# 06_ZYNQ_CAMERALINK.net
KiCad netlist of a schematic drawn in Altium Designer
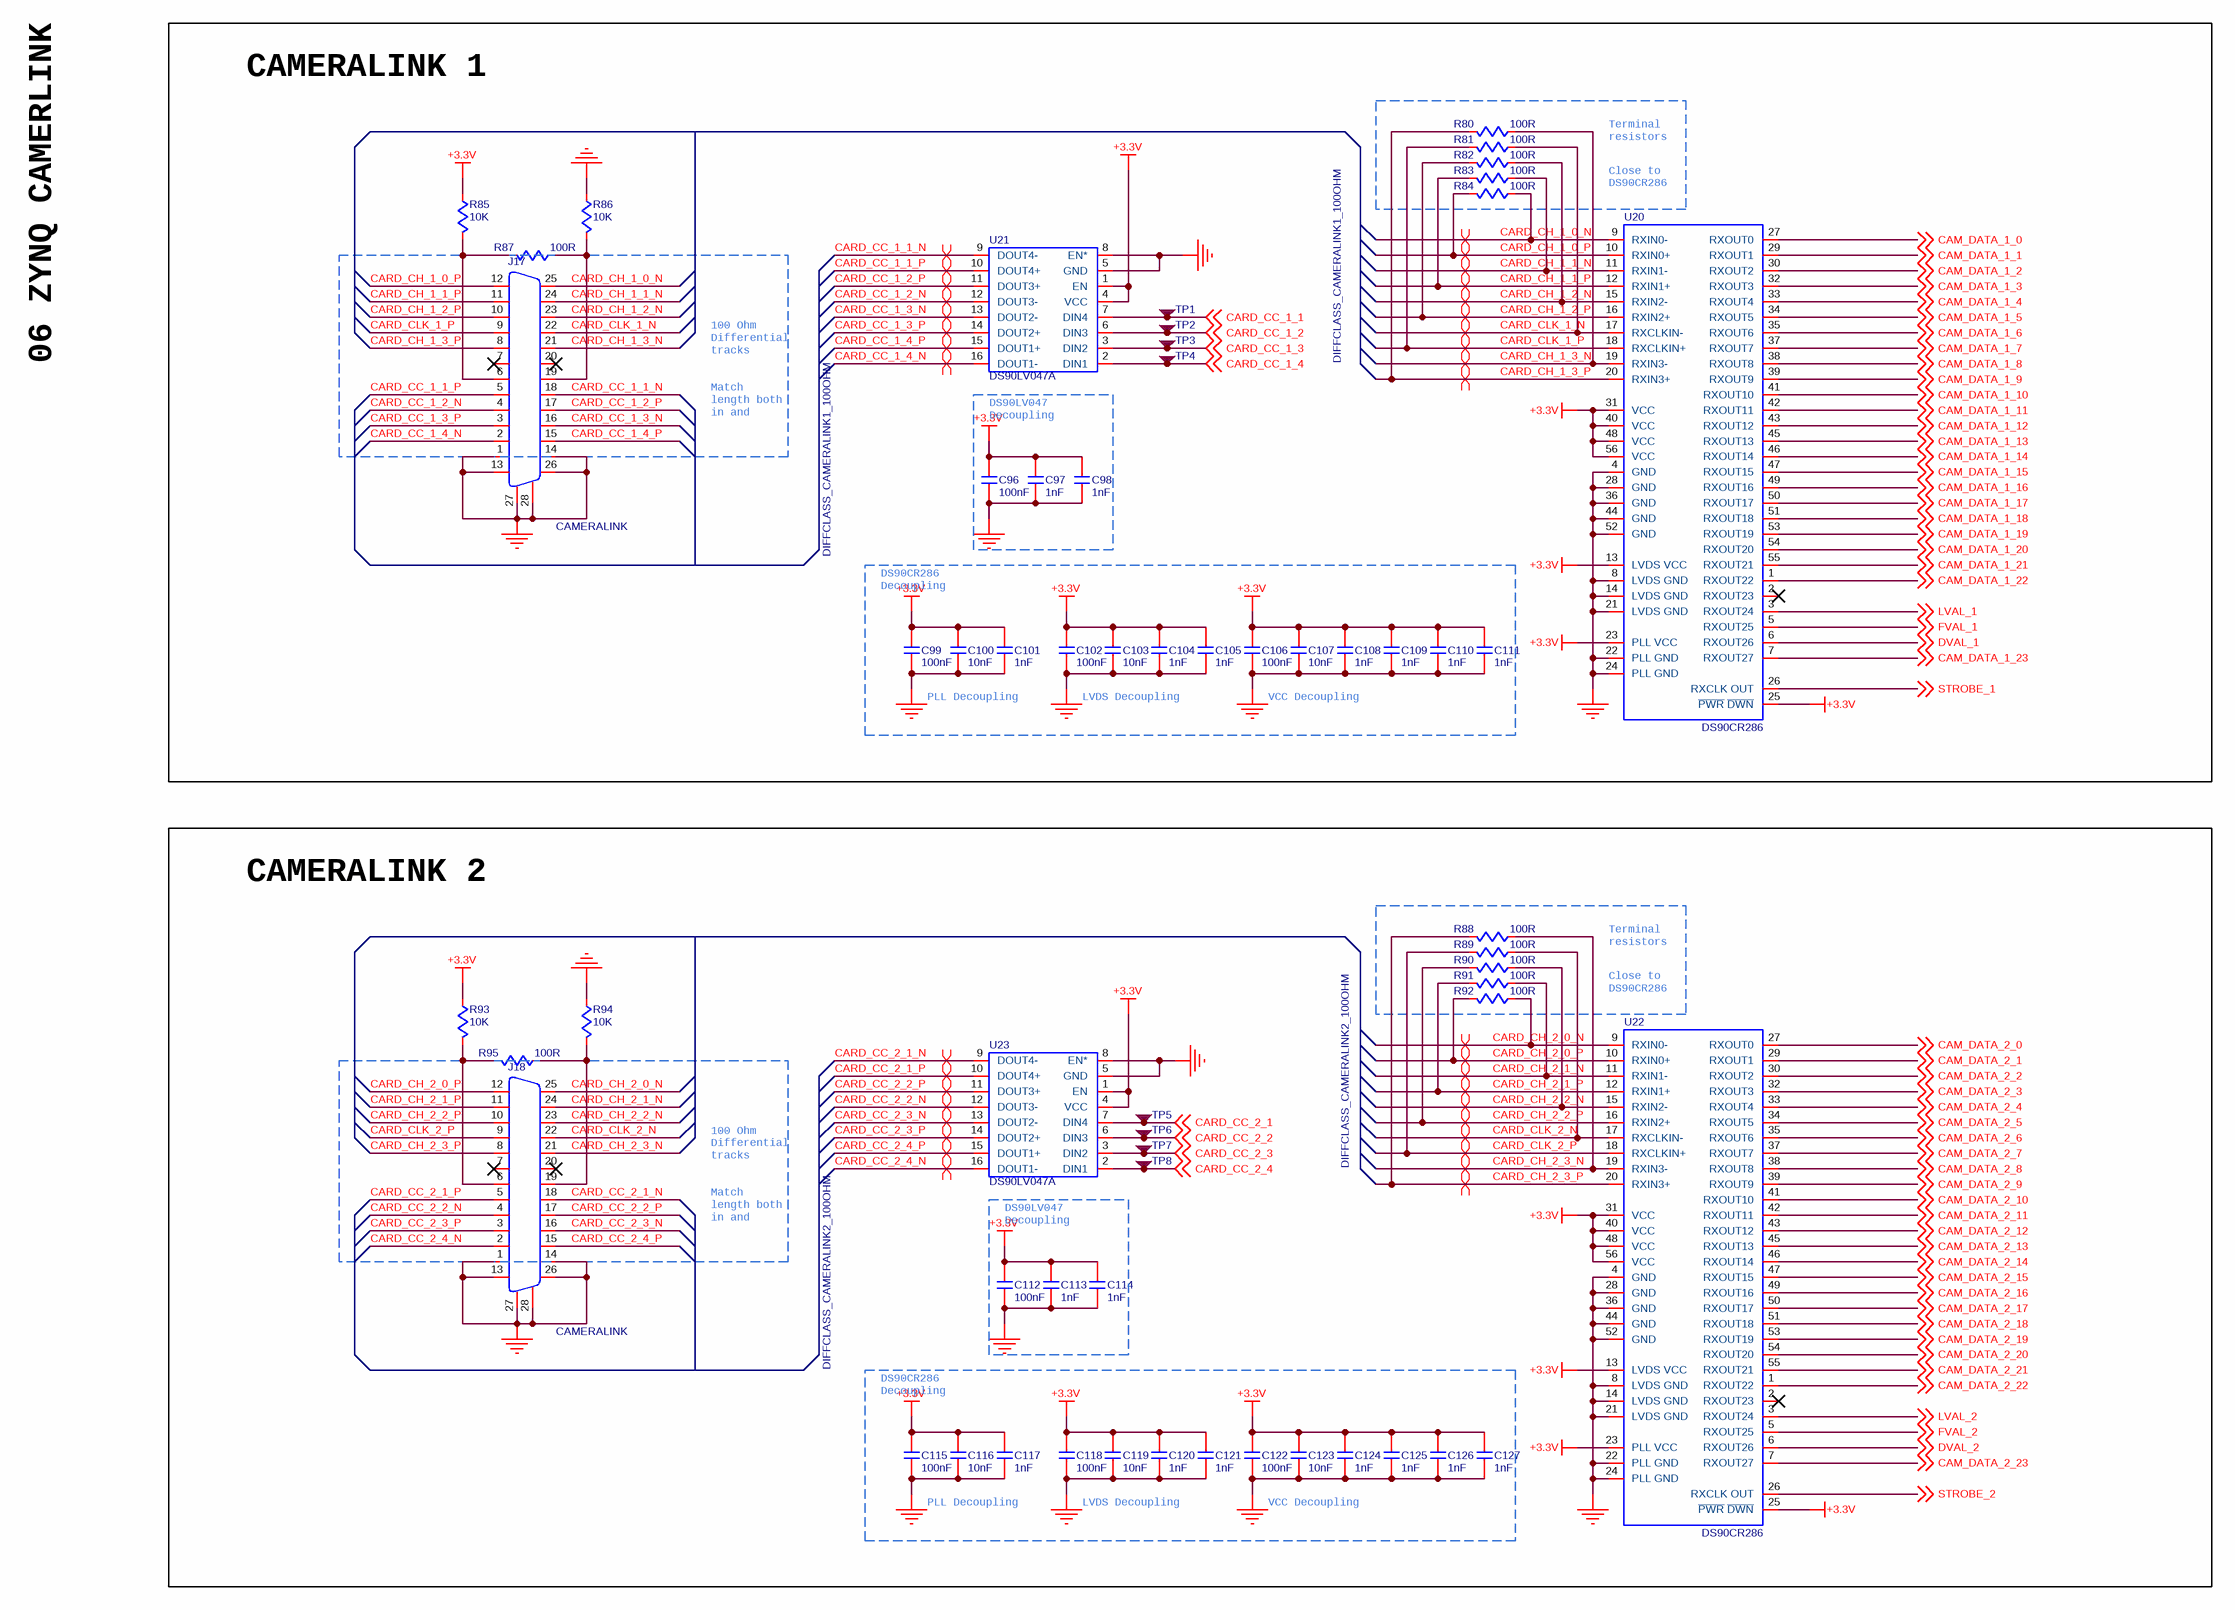
[diagram p0: 06_ZYNQ_CAMERALINK.SchDoc]

(export (version "E")
  (design (tool "Eeschema 10.0.6"))
  (components
    (comp (ref "C96")
      (value "100nF")
      (footprint "zynq:C0402")
      (fields (field (name "VOLTAGE") "25V") (field (name "Comment") "C-NOMO"))
      (libsource (lib "zynq") (part "C-NOMO"))
    )
    (comp (ref "C97")
      (value "1nF")
      (footprint "zynq:C0402")
      (fields (field (name "VOLTAGE") "25V") (field (name "Comment") "C-NOMO"))
      (libsource (lib "zynq") (part "C-NOMO"))
    )
    (comp (ref "C98")
      (value "1nF")
      (footprint "zynq:C0402")
      (fields (field (name "VOLTAGE") "25V") (field (name "Comment") "C-NOMO"))
      (libsource (lib "zynq") (part "C-NOMO"))
    )
    (comp (ref "C99")
      (value "100nF")
      (footprint "zynq:C0402")
      (fields (field (name "VOLTAGE") "25V") (field (name "Comment") "C-NOMO"))
      (libsource (lib "zynq") (part "C-NOMO"))
    )
    (comp (ref "C100")
      (value "10nF")
      (footprint "zynq:C0402")
      (fields (field (name "VOLTAGE") "25V") (field (name "Comment") "C-NOMO"))
      (libsource (lib "zynq") (part "C-NOMO"))
    )
    (comp (ref "C101")
      (value "1nF")
      (footprint "zynq:C0402")
      (fields (field (name "VOLTAGE") "25V") (field (name "Comment") "C-NOMO"))
      (libsource (lib "zynq") (part "C-NOMO"))
    )
    (comp (ref "C102")
      (value "100nF")
      (footprint "zynq:C0402")
      (fields (field (name "VOLTAGE") "25V") (field (name "Comment") "C-NOMO"))
      (libsource (lib "zynq") (part "C-NOMO"))
    )
    (comp (ref "C103")
      (value "10nF")
      (footprint "zynq:C0402")
      (fields (field (name "VOLTAGE") "25V") (field (name "Comment") "C-NOMO"))
      (libsource (lib "zynq") (part "C-NOMO"))
    )
    (comp (ref "C104")
      (value "1nF")
      (footprint "zynq:C0402")
      (fields (field (name "VOLTAGE") "25V") (field (name "Comment") "C-NOMO"))
      (libsource (lib "zynq") (part "C-NOMO"))
    )
    (comp (ref "C105")
      (value "1nF")
      (footprint "zynq:C0402")
      (fields (field (name "VOLTAGE") "25V") (field (name "Comment") "C-NOMO"))
      (libsource (lib "zynq") (part "C-NOMO"))
    )
    (comp (ref "C106")
      (value "100nF")
      (footprint "zynq:C0402")
      (fields (field (name "VOLTAGE") "25V") (field (name "Comment") "C-NOMO"))
      (libsource (lib "zynq") (part "C-NOMO"))
    )
    (comp (ref "C107")
      (value "10nF")
      (footprint "zynq:C0402")
      (fields (field (name "VOLTAGE") "25V") (field (name "Comment") "C-NOMO"))
      (libsource (lib "zynq") (part "C-NOMO"))
    )
    (comp (ref "C108")
      (value "1nF")
      (footprint "zynq:C0402")
      (fields (field (name "VOLTAGE") "25V") (field (name "Comment") "C-NOMO"))
      (libsource (lib "zynq") (part "C-NOMO"))
    )
    (comp (ref "C109")
      (value "1nF")
      (footprint "zynq:C0402")
      (fields (field (name "VOLTAGE") "25V") (field (name "Comment") "C-NOMO"))
      (libsource (lib "zynq") (part "C-NOMO"))
    )
    (comp (ref "C110")
      (value "1nF")
      (footprint "zynq:C0402")
      (fields (field (name "VOLTAGE") "25V") (field (name "Comment") "C-NOMO"))
      (libsource (lib "zynq") (part "C-NOMO"))
    )
    (comp (ref "C111")
      (value "1nF")
      (footprint "zynq:C0402")
      (fields (field (name "VOLTAGE") "25V") (field (name "Comment") "C-NOMO"))
      (libsource (lib "zynq") (part "C-NOMO"))
    )
    (comp (ref "C112")
      (value "100nF")
      (footprint "zynq:C0402")
      (fields (field (name "VOLTAGE") "25V") (field (name "Comment") "C-NOMO"))
      (libsource (lib "zynq") (part "C-NOMO"))
    )
    (comp (ref "C113")
      (value "1nF")
      (footprint "zynq:C0402")
      (fields (field (name "VOLTAGE") "25V") (field (name "Comment") "C-NOMO"))
      (libsource (lib "zynq") (part "C-NOMO"))
    )
    (comp (ref "C114")
      (value "1nF")
      (footprint "zynq:C0402")
      (fields (field (name "VOLTAGE") "25V") (field (name "Comment") "C-NOMO"))
      (libsource (lib "zynq") (part "C-NOMO"))
    )
    (comp (ref "C115")
      (value "100nF")
      (footprint "zynq:C0402")
      (fields (field (name "VOLTAGE") "25V") (field (name "Comment") "C-NOMO"))
      (libsource (lib "zynq") (part "C-NOMO"))
    )
    (comp (ref "C116")
      (value "10nF")
      (footprint "zynq:C0402")
      (fields (field (name "VOLTAGE") "25V") (field (name "Comment") "C-NOMO"))
      (libsource (lib "zynq") (part "C-NOMO"))
    )
    (comp (ref "C117")
      (value "1nF")
      (footprint "zynq:C0402")
      (fields (field (name "VOLTAGE") "25V") (field (name "Comment") "C-NOMO"))
      (libsource (lib "zynq") (part "C-NOMO"))
    )
    (comp (ref "C118")
      (value "100nF")
      (footprint "zynq:C0402")
      (fields (field (name "VOLTAGE") "25V") (field (name "Comment") "C-NOMO"))
      (libsource (lib "zynq") (part "C-NOMO"))
    )
    (comp (ref "C119")
      (value "10nF")
      (footprint "zynq:C0402")
      (fields (field (name "VOLTAGE") "25V") (field (name "Comment") "C-NOMO"))
      (libsource (lib "zynq") (part "C-NOMO"))
    )
    (comp (ref "C120")
      (value "1nF")
      (footprint "zynq:C0402")
      (fields (field (name "VOLTAGE") "25V") (field (name "Comment") "C-NOMO"))
      (libsource (lib "zynq") (part "C-NOMO"))
    )
    (comp (ref "C121")
      (value "1nF")
      (footprint "zynq:C0402")
      (fields (field (name "VOLTAGE") "25V") (field (name "Comment") "C-NOMO"))
      (libsource (lib "zynq") (part "C-NOMO"))
    )
    (comp (ref "C122")
      (value "100nF")
      (footprint "zynq:C0402")
      (fields (field (name "VOLTAGE") "25V") (field (name "Comment") "C-NOMO"))
      (libsource (lib "zynq") (part "C-NOMO"))
    )
    (comp (ref "C123")
      (value "10nF")
      (footprint "zynq:C0402")
      (fields (field (name "VOLTAGE") "25V") (field (name "Comment") "C-NOMO"))
      (libsource (lib "zynq") (part "C-NOMO"))
    )
    (comp (ref "C124")
      (value "1nF")
      (footprint "zynq:C0402")
      (fields (field (name "VOLTAGE") "25V") (field (name "Comment") "C-NOMO"))
      (libsource (lib "zynq") (part "C-NOMO"))
    )
    (comp (ref "C125")
      (value "1nF")
      (footprint "zynq:C0402")
      (fields (field (name "VOLTAGE") "25V") (field (name "Comment") "C-NOMO"))
      (libsource (lib "zynq") (part "C-NOMO"))
    )
    (comp (ref "C126")
      (value "1nF")
      (footprint "zynq:C0402")
      (fields (field (name "VOLTAGE") "25V") (field (name "Comment") "C-NOMO"))
      (libsource (lib "zynq") (part "C-NOMO"))
    )
    (comp (ref "C127")
      (value "1nF")
      (footprint "zynq:C0402")
      (fields (field (name "VOLTAGE") "25V") (field (name "Comment") "C-NOMO"))
      (libsource (lib "zynq") (part "C-NOMO"))
    )
    (comp (ref "J17")
      (value "CAMERALINK")
      (footprint "zynq:CAMERALINK")
      (libsource (lib "zynq") (part "CAMERALINK"))
    )
    (comp (ref "J18")
      (value "CAMERALINK")
      (footprint "zynq:CAMERALINK")
      (libsource (lib "zynq") (part "CAMERALINK"))
    )
    (comp (ref "R80")
      (value "100R")
      (footprint "zynq:R0402")
      (fields (field (name "Comment") "R"))
      (libsource (lib "zynq") (part "R"))
    )
    (comp (ref "R81")
      (value "100R")
      (footprint "zynq:R0402")
      (fields (field (name "Comment") "R"))
      (libsource (lib "zynq") (part "R"))
    )
    (comp (ref "R82")
      (value "100R")
      (footprint "zynq:R0402")
      (fields (field (name "Comment") "R"))
      (libsource (lib "zynq") (part "R"))
    )
    (comp (ref "R83")
      (value "100R")
      (footprint "zynq:R0402")
      (fields (field (name "Comment") "R"))
      (libsource (lib "zynq") (part "R"))
    )
    (comp (ref "R84")
      (value "100R")
      (footprint "zynq:R0402")
      (fields (field (name "Comment") "R"))
      (libsource (lib "zynq") (part "R"))
    )
    (comp (ref "R85")
      (value "10K")
      (footprint "zynq:R0402")
      (fields (field (name "Comment") "R"))
      (libsource (lib "zynq") (part "R"))
    )
    (comp (ref "R86")
      (value "10K")
      (footprint "zynq:R0402")
      (fields (field (name "Comment") "R"))
      (libsource (lib "zynq") (part "R"))
    )
    (comp (ref "R87")
      (value "100R")
      (footprint "zynq:R0402")
      (fields (field (name "Comment") "R"))
      (libsource (lib "zynq") (part "R"))
    )
    (comp (ref "R88")
      (value "100R")
      (footprint "zynq:R0402")
      (fields (field (name "Comment") "R"))
      (libsource (lib "zynq") (part "R"))
    )
    (comp (ref "R89")
      (value "100R")
      (footprint "zynq:R0402")
      (fields (field (name "Comment") "R"))
      (libsource (lib "zynq") (part "R"))
    )
    (comp (ref "R90")
      (value "100R")
      (footprint "zynq:R0402")
      (fields (field (name "Comment") "R"))
      (libsource (lib "zynq") (part "R"))
    )
    (comp (ref "R91")
      (value "100R")
      (footprint "zynq:R0402")
      (fields (field (name "Comment") "R"))
      (libsource (lib "zynq") (part "R"))
    )
    (comp (ref "R92")
      (value "100R")
      (footprint "zynq:R0402")
      (fields (field (name "Comment") "R"))
      (libsource (lib "zynq") (part "R"))
    )
    (comp (ref "R93")
      (value "10K")
      (footprint "zynq:R0402")
      (fields (field (name "Comment") "R"))
      (libsource (lib "zynq") (part "R"))
    )
    (comp (ref "R94")
      (value "10K")
      (footprint "zynq:R0402")
      (fields (field (name "Comment") "R"))
      (libsource (lib "zynq") (part "R"))
    )
    (comp (ref "R95")
      (value "100R")
      (footprint "zynq:R0402")
      (fields (field (name "Comment") "R"))
      (libsource (lib "zynq") (part "R"))
    )
    (comp (ref "TP1") (value "TP") (footprint "zynq:TP") (libsource (lib "zynq") (part "TP")))
    (comp (ref "TP2") (value "TP") (footprint "zynq:TP") (libsource (lib "zynq") (part "TP")))
    (comp (ref "TP3") (value "TP") (footprint "zynq:TP") (libsource (lib "zynq") (part "TP")))
    (comp (ref "TP4") (value "TP") (footprint "zynq:TP") (libsource (lib "zynq") (part "TP")))
    (comp (ref "TP5") (value "TP") (footprint "zynq:TP") (libsource (lib "zynq") (part "TP")))
    (comp (ref "TP6") (value "TP") (footprint "zynq:TP") (libsource (lib "zynq") (part "TP")))
    (comp (ref "TP7") (value "TP") (footprint "zynq:TP") (libsource (lib "zynq") (part "TP")))
    (comp (ref "TP8") (value "TP") (footprint "zynq:TP") (libsource (lib "zynq") (part "TP")))
    (comp (ref "U20")
      (value "DS90CR286")
      (footprint "zynq:DS90CR286")
      (libsource (lib "zynq") (part "DS90CR286"))
    )
    (comp (ref "U21")
      (value "DS90LV047A")
      (footprint "zynq:DS90LV047")
      (libsource (lib "zynq") (part "DS90LV047A"))
    )
    (comp (ref "U22")
      (value "DS90CR286")
      (footprint "zynq:DS90CR286")
      (libsource (lib "zynq") (part "DS90CR286"))
    )
    (comp (ref "U23")
      (value "DS90LV047A")
      (footprint "zynq:DS90LV047")
      (libsource (lib "zynq") (part "DS90LV047A"))
    )
  )
  (nets
    (net (code "1") (name "+3.3V") (class "Default")
      (node (ref "C100") (pin "2") (pinfunction "2_2") (pintype "passive"))
      (node (ref "C101") (pin "2") (pinfunction "2_2") (pintype "passive"))
      (node (ref "C102") (pin "2") (pinfunction "2_2") (pintype "passive"))
      (node (ref "C103") (pin "2") (pinfunction "2_2") (pintype "passive"))
      (node (ref "C104") (pin "2") (pinfunction "2_2") (pintype "passive"))
      (node (ref "C105") (pin "2") (pinfunction "2_2") (pintype "passive"))
      (node (ref "C106") (pin "2") (pinfunction "2_2") (pintype "passive"))
      (node (ref "C107") (pin "2") (pinfunction "2_2") (pintype "passive"))
      (node (ref "C108") (pin "2") (pinfunction "2_2") (pintype "passive"))
      (node (ref "C109") (pin "2") (pinfunction "2_2") (pintype "passive"))
      (node (ref "C110") (pin "2") (pinfunction "2_2") (pintype "passive"))
      (node (ref "C111") (pin "2") (pinfunction "2_2") (pintype "passive"))
      (node (ref "C112") (pin "2") (pinfunction "2_2") (pintype "passive"))
      (node (ref "C113") (pin "2") (pinfunction "2_2") (pintype "passive"))
      (node (ref "C114") (pin "2") (pinfunction "2_2") (pintype "passive"))
      (node (ref "C115") (pin "2") (pinfunction "2_2") (pintype "passive"))
      (node (ref "C116") (pin "2") (pinfunction "2_2") (pintype "passive"))
      (node (ref "C117") (pin "2") (pinfunction "2_2") (pintype "passive"))
      (node (ref "C118") (pin "2") (pinfunction "2_2") (pintype "passive"))
      (node (ref "C119") (pin "2") (pinfunction "2_2") (pintype "passive"))
      (node (ref "C120") (pin "2") (pinfunction "2_2") (pintype "passive"))
      (node (ref "C121") (pin "2") (pinfunction "2_2") (pintype "passive"))
      (node (ref "C122") (pin "2") (pinfunction "2_2") (pintype "passive"))
      (node (ref "C123") (pin "2") (pinfunction "2_2") (pintype "passive"))
      (node (ref "C124") (pin "2") (pinfunction "2_2") (pintype "passive"))
      (node (ref "C125") (pin "2") (pinfunction "2_2") (pintype "passive"))
      (node (ref "C126") (pin "2") (pinfunction "2_2") (pintype "passive"))
      (node (ref "C127") (pin "2") (pinfunction "2_2") (pintype "passive"))
      (node (ref "C96") (pin "2") (pinfunction "2_2") (pintype "passive"))
      (node (ref "C97") (pin "2") (pinfunction "2_2") (pintype "passive"))
      (node (ref "C98") (pin "2") (pinfunction "2_2") (pintype "passive"))
      (node (ref "C99") (pin "2") (pinfunction "2_2") (pintype "passive"))
      (node (ref "R85") (pin "2") (pinfunction "2_2") (pintype "passive"))
      (node (ref "R93") (pin "2") (pinfunction "2_2") (pintype "passive"))
      (node (ref "U20") (pin "13") (pinfunction "LVDS_VCC_13") (pintype "passive"))
      (node (ref "U20") (pin "23") (pinfunction "PLL_VCC_23") (pintype "passive"))
      (node (ref "U20") (pin "25") (pinfunction "~{PWR}_~{DWN}_25") (pintype "passive"))
      (node (ref "U20") (pin "31") (pinfunction "VCC_31") (pintype "passive"))
      (node (ref "U20") (pin "40") (pinfunction "VCC_40") (pintype "passive"))
      (node (ref "U20") (pin "48") (pinfunction "VCC_48") (pintype "passive"))
      (node (ref "U20") (pin "56") (pinfunction "VCC_56") (pintype "passive"))
      (node (ref "U21") (pin "1") (pinfunction "EN_1") (pintype "passive"))
      (node (ref "U21") (pin "4") (pinfunction "VCC_4") (pintype "passive"))
      (node (ref "U22") (pin "13") (pinfunction "LVDS_VCC_13") (pintype "passive"))
      (node (ref "U22") (pin "23") (pinfunction "PLL_VCC_23") (pintype "passive"))
      (node (ref "U22") (pin "25") (pinfunction "~{PWR}_~{DWN}_25") (pintype "passive"))
      (node (ref "U22") (pin "31") (pinfunction "VCC_31") (pintype "passive"))
      (node (ref "U22") (pin "40") (pinfunction "VCC_40") (pintype "passive"))
      (node (ref "U22") (pin "48") (pinfunction "VCC_48") (pintype "passive"))
      (node (ref "U22") (pin "56") (pinfunction "VCC_56") (pintype "passive"))
      (node (ref "U23") (pin "1") (pinfunction "EN_1") (pintype "passive"))
      (node (ref "U23") (pin "4") (pinfunction "VCC_4") (pintype "passive"))
    )
    (net (code "2") (name "/CARD_CC_1_1_N") (class "Default")
      (node (ref "J17") (pin "18") (pintype "passive"))
      (node (ref "U21") (pin "9") (pinfunction "DOUT4-_9") (pintype "passive"))
    )
    (net (code "3") (name "/CARD_CC_1_1_P") (class "Default")
      (node (ref "J17") (pin "5") (pintype "passive"))
      (node (ref "U21") (pin "10") (pinfunction "DOUT4+_10") (pintype "passive"))
    )
    (net (code "4") (name "/CARD_CC_1_2_N") (class "Default")
      (node (ref "J17") (pin "4") (pintype "passive"))
      (node (ref "U21") (pin "12") (pinfunction "DOUT3-_12") (pintype "passive"))
    )
    (net (code "5") (name "/CARD_CC_1_2_P") (class "Default")
      (node (ref "J17") (pin "17") (pintype "passive"))
      (node (ref "U21") (pin "11") (pinfunction "DOUT3+_11") (pintype "passive"))
    )
    (net (code "6") (name "/CARD_CC_1_3_N") (class "Default")
      (node (ref "J17") (pin "16") (pintype "passive"))
      (node (ref "U21") (pin "13") (pinfunction "DOUT2-_13") (pintype "passive"))
    )
    (net (code "7") (name "/CARD_CC_1_3_P") (class "Default")
      (node (ref "J17") (pin "3") (pintype "passive"))
      (node (ref "U21") (pin "14") (pinfunction "DOUT2+_14") (pintype "passive"))
    )
    (net (code "8") (name "/CARD_CC_1_4_N") (class "Default")
      (node (ref "J17") (pin "2") (pintype "passive"))
      (node (ref "U21") (pin "16") (pinfunction "DOUT1-_16") (pintype "passive"))
    )
    (net (code "9") (name "/CARD_CC_1_4_P") (class "Default")
      (node (ref "J17") (pin "15") (pintype "passive"))
      (node (ref "U21") (pin "15") (pinfunction "DOUT1+_15") (pintype "passive"))
    )
    (net (code "10") (name "/CARD_CC_2_1_N") (class "Default")
      (node (ref "J18") (pin "18") (pintype "passive"))
      (node (ref "U23") (pin "9") (pinfunction "DOUT4-_9") (pintype "passive"))
    )
    (net (code "11") (name "/CARD_CC_2_1_P") (class "Default")
      (node (ref "J18") (pin "5") (pintype "passive"))
      (node (ref "U23") (pin "10") (pinfunction "DOUT4+_10") (pintype "passive"))
    )
    (net (code "12") (name "/CARD_CC_2_2_N") (class "Default")
      (node (ref "J18") (pin "4") (pintype "passive"))
      (node (ref "U23") (pin "12") (pinfunction "DOUT3-_12") (pintype "passive"))
    )
    (net (code "13") (name "/CARD_CC_2_2_P") (class "Default")
      (node (ref "J18") (pin "17") (pintype "passive"))
      (node (ref "U23") (pin "11") (pinfunction "DOUT3+_11") (pintype "passive"))
    )
    (net (code "14") (name "/CARD_CC_2_3_N") (class "Default")
      (node (ref "J18") (pin "16") (pintype "passive"))
      (node (ref "U23") (pin "13") (pinfunction "DOUT2-_13") (pintype "passive"))
    )
    (net (code "15") (name "/CARD_CC_2_3_P") (class "Default")
      (node (ref "J18") (pin "3") (pintype "passive"))
      (node (ref "U23") (pin "14") (pinfunction "DOUT2+_14") (pintype "passive"))
    )
    (net (code "16") (name "/CARD_CC_2_4_N") (class "Default")
      (node (ref "J18") (pin "2") (pintype "passive"))
      (node (ref "U23") (pin "16") (pinfunction "DOUT1-_16") (pintype "passive"))
    )
    (net (code "17") (name "/CARD_CC_2_4_P") (class "Default")
      (node (ref "J18") (pin "15") (pintype "passive"))
      (node (ref "U23") (pin "15") (pinfunction "DOUT1+_15") (pintype "passive"))
    )
    (net (code "18") (name "/CARD_CH_1_0_N") (class "Default")
      (node (ref "J17") (pin "25") (pintype "passive"))
      (node (ref "R84") (pin "2") (pinfunction "2_2") (pintype "passive"))
      (node (ref "U20") (pin "9") (pinfunction "RXIN0-_9") (pintype "passive"))
    )
    (net (code "19") (name "/CARD_CH_1_0_P") (class "Default")
      (node (ref "J17") (pin "12") (pintype "passive"))
      (node (ref "R84") (pin "1") (pinfunction "1_1") (pintype "passive"))
      (node (ref "U20") (pin "10") (pinfunction "RXIN0+_10") (pintype "passive"))
    )
    (net (code "20") (name "/CARD_CH_1_1_N") (class "Default")
      (node (ref "J17") (pin "24") (pintype "passive"))
      (node (ref "R83") (pin "2") (pinfunction "2_2") (pintype "passive"))
      (node (ref "U20") (pin "11") (pinfunction "RXIN1-_11") (pintype "passive"))
    )
    (net (code "21") (name "/CARD_CH_1_1_P") (class "Default")
      (node (ref "J17") (pin "11") (pintype "passive"))
      (node (ref "R83") (pin "1") (pinfunction "1_1") (pintype "passive"))
      (node (ref "U20") (pin "12") (pinfunction "RXIN1+_12") (pintype "passive"))
    )
    (net (code "22") (name "/CARD_CH_1_2_N") (class "Default")
      (node (ref "J17") (pin "23") (pintype "passive"))
      (node (ref "R82") (pin "2") (pinfunction "2_2") (pintype "passive"))
      (node (ref "U20") (pin "15") (pinfunction "RXIN2-_15") (pintype "passive"))
    )
    (net (code "23") (name "/CARD_CH_1_2_P") (class "Default")
      (node (ref "J17") (pin "10") (pintype "passive"))
      (node (ref "R82") (pin "1") (pinfunction "1_1") (pintype "passive"))
      (node (ref "U20") (pin "16") (pinfunction "RXIN2+_16") (pintype "passive"))
    )
    (net (code "24") (name "/CARD_CH_1_3_N") (class "Default")
      (node (ref "J17") (pin "21") (pintype "passive"))
      (node (ref "R80") (pin "2") (pinfunction "2_2") (pintype "passive"))
      (node (ref "U20") (pin "19") (pinfunction "RXIN3-_19") (pintype "passive"))
    )
    (net (code "25") (name "/CARD_CH_1_3_P") (class "Default")
      (node (ref "J17") (pin "8") (pintype "passive"))
      (node (ref "R80") (pin "1") (pinfunction "1_1") (pintype "passive"))
      (node (ref "U20") (pin "20") (pinfunction "RXIN3+_20") (pintype "passive"))
    )
    (net (code "26") (name "/CARD_CH_2_0_N") (class "Default")
      (node (ref "J18") (pin "25") (pintype "passive"))
      (node (ref "R92") (pin "2") (pinfunction "2_2") (pintype "passive"))
      (node (ref "U22") (pin "9") (pinfunction "RXIN0-_9") (pintype "passive"))
    )
    (net (code "27") (name "/CARD_CH_2_0_P") (class "Default")
      (node (ref "J18") (pin "12") (pintype "passive"))
      (node (ref "R92") (pin "1") (pinfunction "1_1") (pintype "passive"))
      (node (ref "U22") (pin "10") (pinfunction "RXIN0+_10") (pintype "passive"))
    )
    (net (code "28") (name "/CARD_CH_2_1_N") (class "Default")
      (node (ref "J18") (pin "24") (pintype "passive"))
      (node (ref "R91") (pin "2") (pinfunction "2_2") (pintype "passive"))
      (node (ref "U22") (pin "11") (pinfunction "RXIN1-_11") (pintype "passive"))
    )
    (net (code "29") (name "/CARD_CH_2_1_P") (class "Default")
      (node (ref "J18") (pin "11") (pintype "passive"))
      (node (ref "R91") (pin "1") (pinfunction "1_1") (pintype "passive"))
      (node (ref "U22") (pin "12") (pinfunction "RXIN1+_12") (pintype "passive"))
    )
    (net (code "30") (name "/CARD_CH_2_2_N") (class "Default")
      (node (ref "J18") (pin "23") (pintype "passive"))
      (node (ref "R90") (pin "2") (pinfunction "2_2") (pintype "passive"))
      (node (ref "U22") (pin "15") (pinfunction "RXIN2-_15") (pintype "passive"))
    )
    (net (code "31") (name "/CARD_CH_2_2_P") (class "Default")
      (node (ref "J18") (pin "10") (pintype "passive"))
      (node (ref "R90") (pin "1") (pinfunction "1_1") (pintype "passive"))
      (node (ref "U22") (pin "16") (pinfunction "RXIN2+_16") (pintype "passive"))
    )
    (net (code "32") (name "/CARD_CH_2_3_N") (class "Default")
      (node (ref "J18") (pin "21") (pintype "passive"))
      (node (ref "R88") (pin "2") (pinfunction "2_2") (pintype "passive"))
      (node (ref "U22") (pin "19") (pinfunction "RXIN3-_19") (pintype "passive"))
    )
    (net (code "33") (name "/CARD_CH_2_3_P") (class "Default")
      (node (ref "J18") (pin "8") (pintype "passive"))
      (node (ref "R88") (pin "1") (pinfunction "1_1") (pintype "passive"))
      (node (ref "U22") (pin "20") (pinfunction "RXIN3+_20") (pintype "passive"))
    )
    (net (code "34") (name "/CARD_CLK_1_N") (class "Default")
      (node (ref "J17") (pin "22") (pintype "passive"))
      (node (ref "R81") (pin "2") (pinfunction "2_2") (pintype "passive"))
      (node (ref "U20") (pin "17") (pinfunction "RXCLKIN-_17") (pintype "passive"))
    )
    (net (code "35") (name "/CARD_CLK_1_P") (class "Default")
      (node (ref "J17") (pin "9") (pintype "passive"))
      (node (ref "R81") (pin "1") (pinfunction "1_1") (pintype "passive"))
      (node (ref "U20") (pin "18") (pinfunction "RXCLKIN+_18") (pintype "passive"))
    )
    (net (code "36") (name "/CARD_CLK_2_N") (class "Default")
      (node (ref "J18") (pin "22") (pintype "passive"))
      (node (ref "R89") (pin "2") (pinfunction "2_2") (pintype "passive"))
      (node (ref "U22") (pin "17") (pinfunction "RXCLKIN-_17") (pintype "passive"))
    )
    (net (code "37") (name "/CARD_CLK_2_P") (class "Default")
      (node (ref "J18") (pin "9") (pintype "passive"))
      (node (ref "R89") (pin "1") (pinfunction "1_1") (pintype "passive"))
      (node (ref "U22") (pin "18") (pinfunction "RXCLKIN+_18") (pintype "passive"))
    )
    (net (code "38") (name "CAM_DATA_1_0") (class "Default")
      (node (ref "U20") (pin "27") (pinfunction "RXOUT0_27") (pintype "passive"))
    )
    (net (code "39") (name "CAM_DATA_1_1") (class "Default")
      (node (ref "U20") (pin "29") (pinfunction "RXOUT1_29") (pintype "passive"))
    )
    (net (code "40") (name "CAM_DATA_1_2") (class "Default")
      (node (ref "U20") (pin "30") (pinfunction "RXOUT2_30") (pintype "passive"))
    )
    (net (code "41") (name "CAM_DATA_1_3") (class "Default")
      (node (ref "U20") (pin "32") (pinfunction "RXOUT3_32") (pintype "passive"))
    )
    (net (code "42") (name "CAM_DATA_1_4") (class "Default")
      (node (ref "U20") (pin "33") (pinfunction "RXOUT4_33") (pintype "passive"))
    )
    (net (code "43") (name "CAM_DATA_1_5") (class "Default")
      (node (ref "U20") (pin "34") (pinfunction "RXOUT5_34") (pintype "passive"))
    )
    (net (code "44") (name "CAM_DATA_1_6") (class "Default")
      (node (ref "U20") (pin "35") (pinfunction "RXOUT6_35") (pintype "passive"))
    )
    (net (code "45") (name "CAM_DATA_1_7") (class "Default")
      (node (ref "U20") (pin "37") (pinfunction "RXOUT7_37") (pintype "passive"))
    )
    (net (code "46") (name "CAM_DATA_1_8") (class "Default")
      (node (ref "U20") (pin "38") (pinfunction "RXOUT8_38") (pintype "passive"))
    )
    (net (code "47") (name "CAM_DATA_1_9") (class "Default")
      (node (ref "U20") (pin "39") (pinfunction "RXOUT9_39") (pintype "passive"))
    )
    (net (code "48") (name "CAM_DATA_1_10") (class "Default")
      (node (ref "U20") (pin "41") (pinfunction "RXOUT10_41") (pintype "passive"))
    )
    (net (code "49") (name "CAM_DATA_1_11") (class "Default")
      (node (ref "U20") (pin "42") (pinfunction "RXOUT11_42") (pintype "passive"))
    )
    (net (code "50") (name "CAM_DATA_1_12") (class "Default")
      (node (ref "U20") (pin "43") (pinfunction "RXOUT12_43") (pintype "passive"))
    )
    (net (code "51") (name "CAM_DATA_1_13") (class "Default")
      (node (ref "U20") (pin "45") (pinfunction "RXOUT13_45") (pintype "passive"))
    )
    (net (code "52") (name "CAM_DATA_1_14") (class "Default")
      (node (ref "U20") (pin "46") (pinfunction "RXOUT14_46") (pintype "passive"))
    )
    (net (code "53") (name "CAM_DATA_1_15") (class "Default")
      (node (ref "U20") (pin "47") (pinfunction "RXOUT15_47") (pintype "passive"))
    )
    (net (code "54") (name "CAM_DATA_1_16") (class "Default")
      (node (ref "U20") (pin "49") (pinfunction "RXOUT16_49") (pintype "passive"))
    )
    (net (code "55") (name "CAM_DATA_1_17") (class "Default")
      (node (ref "U20") (pin "50") (pinfunction "RXOUT17_50") (pintype "passive"))
    )
    (net (code "56") (name "CAM_DATA_1_18") (class "Default")
      (node (ref "U20") (pin "51") (pinfunction "RXOUT18_51") (pintype "passive"))
    )
    (net (code "57") (name "CAM_DATA_1_19") (class "Default")
      (node (ref "U20") (pin "53") (pinfunction "RXOUT19_53") (pintype "passive"))
    )
    (net (code "58") (name "CAM_DATA_1_20") (class "Default")
      (node (ref "U20") (pin "54") (pinfunction "RXOUT20_54") (pintype "passive"))
    )
    (net (code "59") (name "CAM_DATA_1_21") (class "Default")
      (node (ref "U20") (pin "55") (pinfunction "RXOUT21_55") (pintype "passive"))
    )
    (net (code "60") (name "CAM_DATA_1_22") (class "Default")
      (node (ref "U20") (pin "1") (pinfunction "RXOUT22_1") (pintype "passive"))
    )
    (net (code "61") (name "CAM_DATA_1_23") (class "Default")
      (node (ref "U20") (pin "7") (pinfunction "RXOUT27_7") (pintype "passive"))
    )
    (net (code "62") (name "CAM_DATA_2_0") (class "Default")
      (node (ref "U22") (pin "27") (pinfunction "RXOUT0_27") (pintype "passive"))
    )
    (net (code "63") (name "CAM_DATA_2_1") (class "Default")
      (node (ref "U22") (pin "29") (pinfunction "RXOUT1_29") (pintype "passive"))
    )
    (net (code "64") (name "CAM_DATA_2_2") (class "Default")
      (node (ref "U22") (pin "30") (pinfunction "RXOUT2_30") (pintype "passive"))
    )
    (net (code "65") (name "CAM_DATA_2_3") (class "Default")
      (node (ref "U22") (pin "32") (pinfunction "RXOUT3_32") (pintype "passive"))
    )
    (net (code "66") (name "CAM_DATA_2_4") (class "Default")
      (node (ref "U22") (pin "33") (pinfunction "RXOUT4_33") (pintype "passive"))
    )
    (net (code "67") (name "CAM_DATA_2_5") (class "Default")
      (node (ref "U22") (pin "34") (pinfunction "RXOUT5_34") (pintype "passive"))
    )
    (net (code "68") (name "CAM_DATA_2_6") (class "Default")
      (node (ref "U22") (pin "35") (pinfunction "RXOUT6_35") (pintype "passive"))
    )
    (net (code "69") (name "CAM_DATA_2_7") (class "Default")
      (node (ref "U22") (pin "37") (pinfunction "RXOUT7_37") (pintype "passive"))
    )
    (net (code "70") (name "CAM_DATA_2_8") (class "Default")
      (node (ref "U22") (pin "38") (pinfunction "RXOUT8_38") (pintype "passive"))
    )
    (net (code "71") (name "CAM_DATA_2_9") (class "Default")
      (node (ref "U22") (pin "39") (pinfunction "RXOUT9_39") (pintype "passive"))
    )
    (net (code "72") (name "CAM_DATA_2_10") (class "Default")
      (node (ref "U22") (pin "41") (pinfunction "RXOUT10_41") (pintype "passive"))
    )
    (net (code "73") (name "CAM_DATA_2_11") (class "Default")
      (node (ref "U22") (pin "42") (pinfunction "RXOUT11_42") (pintype "passive"))
    )
    (net (code "74") (name "CAM_DATA_2_12") (class "Default")
      (node (ref "U22") (pin "43") (pinfunction "RXOUT12_43") (pintype "passive"))
    )
    (net (code "75") (name "CAM_DATA_2_13") (class "Default")
      (node (ref "U22") (pin "45") (pinfunction "RXOUT13_45") (pintype "passive"))
    )
    (net (code "76") (name "CAM_DATA_2_14") (class "Default")
      (node (ref "U22") (pin "46") (pinfunction "RXOUT14_46") (pintype "passive"))
    )
    (net (code "77") (name "CAM_DATA_2_15") (class "Default")
      (node (ref "U22") (pin "47") (pinfunction "RXOUT15_47") (pintype "passive"))
    )
    (net (code "78") (name "CAM_DATA_2_16") (class "Default")
      (node (ref "U22") (pin "49") (pinfunction "RXOUT16_49") (pintype "passive"))
    )
    (net (code "79") (name "CAM_DATA_2_17") (class "Default")
      (node (ref "U22") (pin "50") (pinfunction "RXOUT17_50") (pintype "passive"))
    )
    (net (code "80") (name "CAM_DATA_2_18") (class "Default")
      (node (ref "U22") (pin "51") (pinfunction "RXOUT18_51") (pintype "passive"))
    )
    (net (code "81") (name "CAM_DATA_2_19") (class "Default")
      (node (ref "U22") (pin "53") (pinfunction "RXOUT19_53") (pintype "passive"))
    )
    (net (code "82") (name "CAM_DATA_2_20") (class "Default")
      (node (ref "U22") (pin "54") (pinfunction "RXOUT20_54") (pintype "passive"))
    )
    (net (code "83") (name "CAM_DATA_2_21") (class "Default")
      (node (ref "U22") (pin "55") (pinfunction "RXOUT21_55") (pintype "passive"))
    )
    (net (code "84") (name "CAM_DATA_2_22") (class "Default")
      (node (ref "U22") (pin "1") (pinfunction "RXOUT22_1") (pintype "passive"))
    )
    (net (code "85") (name "CAM_DATA_2_23") (class "Default")
      (node (ref "U22") (pin "7") (pinfunction "RXOUT27_7") (pintype "passive"))
    )
    (net (code "86") (name "CARD_CC_1_1") (class "Default")
      (node (ref "TP1") (pin "0") (pintype "passive"))
      (node (ref "U21") (pin "7") (pinfunction "DIN4_7") (pintype "passive"))
    )
    (net (code "87") (name "CARD_CC_1_2") (class "Default")
      (node (ref "TP2") (pin "0") (pintype "passive"))
      (node (ref "U21") (pin "6") (pinfunction "DIN3_6") (pintype "passive"))
    )
    (net (code "88") (name "CARD_CC_1_3") (class "Default")
      (node (ref "TP3") (pin "0") (pintype "passive"))
      (node (ref "U21") (pin "3") (pinfunction "DIN2_3") (pintype "passive"))
    )
    (net (code "89") (name "CARD_CC_1_4") (class "Default")
      (node (ref "TP4") (pin "0") (pintype "passive"))
      (node (ref "U21") (pin "2") (pinfunction "DIN1_2") (pintype "passive"))
    )
    (net (code "90") (name "CARD_CC_2_1") (class "Default")
      (node (ref "TP5") (pin "0") (pintype "passive"))
      (node (ref "U23") (pin "7") (pinfunction "DIN4_7") (pintype "passive"))
    )
    (net (code "91") (name "CARD_CC_2_2") (class "Default")
      (node (ref "TP6") (pin "0") (pintype "passive"))
      (node (ref "U23") (pin "6") (pinfunction "DIN3_6") (pintype "passive"))
    )
    (net (code "92") (name "CARD_CC_2_3") (class "Default")
      (node (ref "TP7") (pin "0") (pintype "passive"))
      (node (ref "U23") (pin "3") (pinfunction "DIN2_3") (pintype "passive"))
    )
    (net (code "93") (name "CARD_CC_2_4") (class "Default")
      (node (ref "TP8") (pin "0") (pintype "passive"))
      (node (ref "U23") (pin "2") (pinfunction "DIN1_2") (pintype "passive"))
    )
    (net (code "94") (name "DVAL_1") (class "Default")
      (node (ref "U20") (pin "6") (pinfunction "RXOUT26_6") (pintype "passive"))
    )
    (net (code "95") (name "DVAL_2") (class "Default")
      (node (ref "U22") (pin "6") (pinfunction "RXOUT26_6") (pintype "passive"))
    )
    (net (code "96") (name "FVAL_1") (class "Default")
      (node (ref "U20") (pin "5") (pinfunction "RXOUT25_5") (pintype "passive"))
    )
    (net (code "97") (name "FVAL_2") (class "Default")
      (node (ref "U22") (pin "5") (pinfunction "RXOUT25_5") (pintype "passive"))
    )
    (net (code "98") (name "GND") (class "Default")
      (node (ref "C100") (pin "1") (pinfunction "1_1") (pintype "passive"))
      (node (ref "C101") (pin "1") (pinfunction "1_1") (pintype "passive"))
      (node (ref "C102") (pin "1") (pinfunction "1_1") (pintype "passive"))
      (node (ref "C103") (pin "1") (pinfunction "1_1") (pintype "passive"))
      (node (ref "C104") (pin "1") (pinfunction "1_1") (pintype "passive"))
      (node (ref "C105") (pin "1") (pinfunction "1_1") (pintype "passive"))
      (node (ref "C106") (pin "1") (pinfunction "1_1") (pintype "passive"))
      (node (ref "C107") (pin "1") (pinfunction "1_1") (pintype "passive"))
      (node (ref "C108") (pin "1") (pinfunction "1_1") (pintype "passive"))
      (node (ref "C109") (pin "1") (pinfunction "1_1") (pintype "passive"))
      (node (ref "C110") (pin "1") (pinfunction "1_1") (pintype "passive"))
      (node (ref "C111") (pin "1") (pinfunction "1_1") (pintype "passive"))
      (node (ref "C112") (pin "1") (pinfunction "1_1") (pintype "passive"))
      (node (ref "C113") (pin "1") (pinfunction "1_1") (pintype "passive"))
      (node (ref "C114") (pin "1") (pinfunction "1_1") (pintype "passive"))
      (node (ref "C115") (pin "1") (pinfunction "1_1") (pintype "passive"))
      (node (ref "C116") (pin "1") (pinfunction "1_1") (pintype "passive"))
      (node (ref "C117") (pin "1") (pinfunction "1_1") (pintype "passive"))
      (node (ref "C118") (pin "1") (pinfunction "1_1") (pintype "passive"))
      (node (ref "C119") (pin "1") (pinfunction "1_1") (pintype "passive"))
      (node (ref "C120") (pin "1") (pinfunction "1_1") (pintype "passive"))
      (node (ref "C121") (pin "1") (pinfunction "1_1") (pintype "passive"))
      (node (ref "C122") (pin "1") (pinfunction "1_1") (pintype "passive"))
      (node (ref "C123") (pin "1") (pinfunction "1_1") (pintype "passive"))
      (node (ref "C124") (pin "1") (pinfunction "1_1") (pintype "passive"))
      (node (ref "C125") (pin "1") (pinfunction "1_1") (pintype "passive"))
      (node (ref "C126") (pin "1") (pinfunction "1_1") (pintype "passive"))
      (node (ref "C127") (pin "1") (pinfunction "1_1") (pintype "passive"))
      (node (ref "C96") (pin "1") (pinfunction "1_1") (pintype "passive"))
      (node (ref "C97") (pin "1") (pinfunction "1_1") (pintype "passive"))
      (node (ref "C98") (pin "1") (pinfunction "1_1") (pintype "passive"))
      (node (ref "C99") (pin "1") (pinfunction "1_1") (pintype "passive"))
      (node (ref "J17") (pin "1") (pintype "passive"))
      (node (ref "J17") (pin "13") (pintype "passive"))
      (node (ref "J17") (pin "14") (pintype "passive"))
      (node (ref "J17") (pin "26") (pintype "passive"))
      (node (ref "J17") (pin "27") (pinfunction "27_27") (pintype "passive"))
      (node (ref "J17") (pin "28") (pinfunction "28_28") (pintype "passive"))
      (node (ref "J18") (pin "1") (pintype "passive"))
      (node (ref "J18") (pin "13") (pintype "passive"))
      (node (ref "J18") (pin "14") (pintype "passive"))
      (node (ref "J18") (pin "26") (pintype "passive"))
      (node (ref "J18") (pin "27") (pinfunction "27_27") (pintype "passive"))
      (node (ref "J18") (pin "28") (pinfunction "28_28") (pintype "passive"))
      (node (ref "R86") (pin "2") (pinfunction "2_2") (pintype "passive"))
      (node (ref "R94") (pin "2") (pinfunction "2_2") (pintype "passive"))
      (node (ref "U20") (pin "14") (pinfunction "LVDS_GND_14") (pintype "passive"))
      (node (ref "U20") (pin "21") (pinfunction "LVDS_GND_21") (pintype "passive"))
      (node (ref "U20") (pin "22") (pinfunction "PLL_GND_22") (pintype "passive"))
      (node (ref "U20") (pin "24") (pinfunction "PLL_GND_24") (pintype "passive"))
      (node (ref "U20") (pin "28") (pinfunction "GND_28") (pintype "passive"))
      (node (ref "U20") (pin "36") (pinfunction "GND_36") (pintype "passive"))
      (node (ref "U20") (pin "4") (pinfunction "GND_4") (pintype "passive"))
      (node (ref "U20") (pin "44") (pinfunction "GND_44") (pintype "passive"))
      (node (ref "U20") (pin "52") (pinfunction "GND_52") (pintype "passive"))
      (node (ref "U20") (pin "8") (pinfunction "LVDS_GND_8") (pintype "passive"))
      (node (ref "U21") (pin "5") (pinfunction "GND_5") (pintype "passive"))
      (node (ref "U21") (pin "8") (pinfunction "EN*_8") (pintype "passive"))
      (node (ref "U22") (pin "14") (pinfunction "LVDS_GND_14") (pintype "passive"))
      (node (ref "U22") (pin "21") (pinfunction "LVDS_GND_21") (pintype "passive"))
      (node (ref "U22") (pin "22") (pinfunction "PLL_GND_22") (pintype "passive"))
      (node (ref "U22") (pin "24") (pinfunction "PLL_GND_24") (pintype "passive"))
      (node (ref "U22") (pin "28") (pinfunction "GND_28") (pintype "passive"))
      (node (ref "U22") (pin "36") (pinfunction "GND_36") (pintype "passive"))
      (node (ref "U22") (pin "4") (pinfunction "GND_4") (pintype "passive"))
      (node (ref "U22") (pin "44") (pinfunction "GND_44") (pintype "passive"))
      (node (ref "U22") (pin "52") (pinfunction "GND_52") (pintype "passive"))
      (node (ref "U22") (pin "8") (pinfunction "LVDS_GND_8") (pintype "passive"))
      (node (ref "U23") (pin "5") (pinfunction "GND_5") (pintype "passive"))
      (node (ref "U23") (pin "8") (pinfunction "EN*_8") (pintype "passive"))
    )
    (net (code "99") (name "LVAL_1") (class "Default")
      (node (ref "U20") (pin "3") (pinfunction "RXOUT24_3") (pintype "passive"))
    )
    (net (code "100") (name "LVAL_2") (class "Default")
      (node (ref "U22") (pin "3") (pinfunction "RXOUT24_3") (pintype "passive"))
    )
    (net (code "101") (name "Net-(J17-Pad6)") (class "Default")
      (node (ref "J17") (pin "6") (pintype "passive"))
      (node (ref "R85") (pin "1") (pinfunction "1_1") (pintype "passive"))
      (node (ref "R87") (pin "1") (pinfunction "1_1") (pintype "passive"))
    )
    (net (code "102") (name "Net-(J17-Pad19)") (class "Default")
      (node (ref "J17") (pin "19") (pintype "passive"))
      (node (ref "R86") (pin "1") (pinfunction "1_1") (pintype "passive"))
      (node (ref "R87") (pin "2") (pinfunction "2_2") (pintype "passive"))
    )
    (net (code "103") (name "Net-(J18-Pad6)") (class "Default")
      (node (ref "J18") (pin "6") (pintype "passive"))
      (node (ref "R93") (pin "1") (pinfunction "1_1") (pintype "passive"))
      (node (ref "R95") (pin "1") (pinfunction "1_1") (pintype "passive"))
    )
    (net (code "104") (name "Net-(J18-Pad19)") (class "Default")
      (node (ref "J18") (pin "19") (pintype "passive"))
      (node (ref "R94") (pin "1") (pinfunction "1_1") (pintype "passive"))
      (node (ref "R95") (pin "2") (pinfunction "2_2") (pintype "passive"))
    )
    (net (code "105") (name "STROBE_1") (class "Default")
      (node (ref "U20") (pin "26") (pinfunction "RXCLK_OUT_26") (pintype "passive"))
    )
    (net (code "106") (name "STROBE_2") (class "Default")
      (node (ref "U22") (pin "26") (pinfunction "RXCLK_OUT_26") (pintype "passive"))
    )
    (net (code "107") (name "unconnected-(J17-Pad7)") (class "Default")
      (node (ref "J17") (pin "7") (pintype "passive+no_connect"))
    )
    (net (code "108") (name "unconnected-(J17-Pad20)") (class "Default")
      (node (ref "J17") (pin "20") (pintype "passive+no_connect"))
    )
    (net (code "109") (name "unconnected-(J18-Pad7)") (class "Default")
      (node (ref "J18") (pin "7") (pintype "passive+no_connect"))
    )
    (net (code "110") (name "unconnected-(J18-Pad20)") (class "Default")
      (node (ref "J18") (pin "20") (pintype "passive+no_connect"))
    )
    (net (code "111") (name "unconnected-(U20-RXOUT23-Pad2)") (class "Default")
      (node (ref "U20") (pin "2") (pinfunction "RXOUT23_2") (pintype "passive+no_connect"))
    )
    (net (code "112") (name "unconnected-(U22-RXOUT23-Pad2)") (class "Default")
      (node (ref "U22") (pin "2") (pinfunction "RXOUT23_2") (pintype "passive+no_connect"))
    )
  )
)
